# Electronic_Dice.net
KiCad netlist of a schematic drawn in Altium Designer
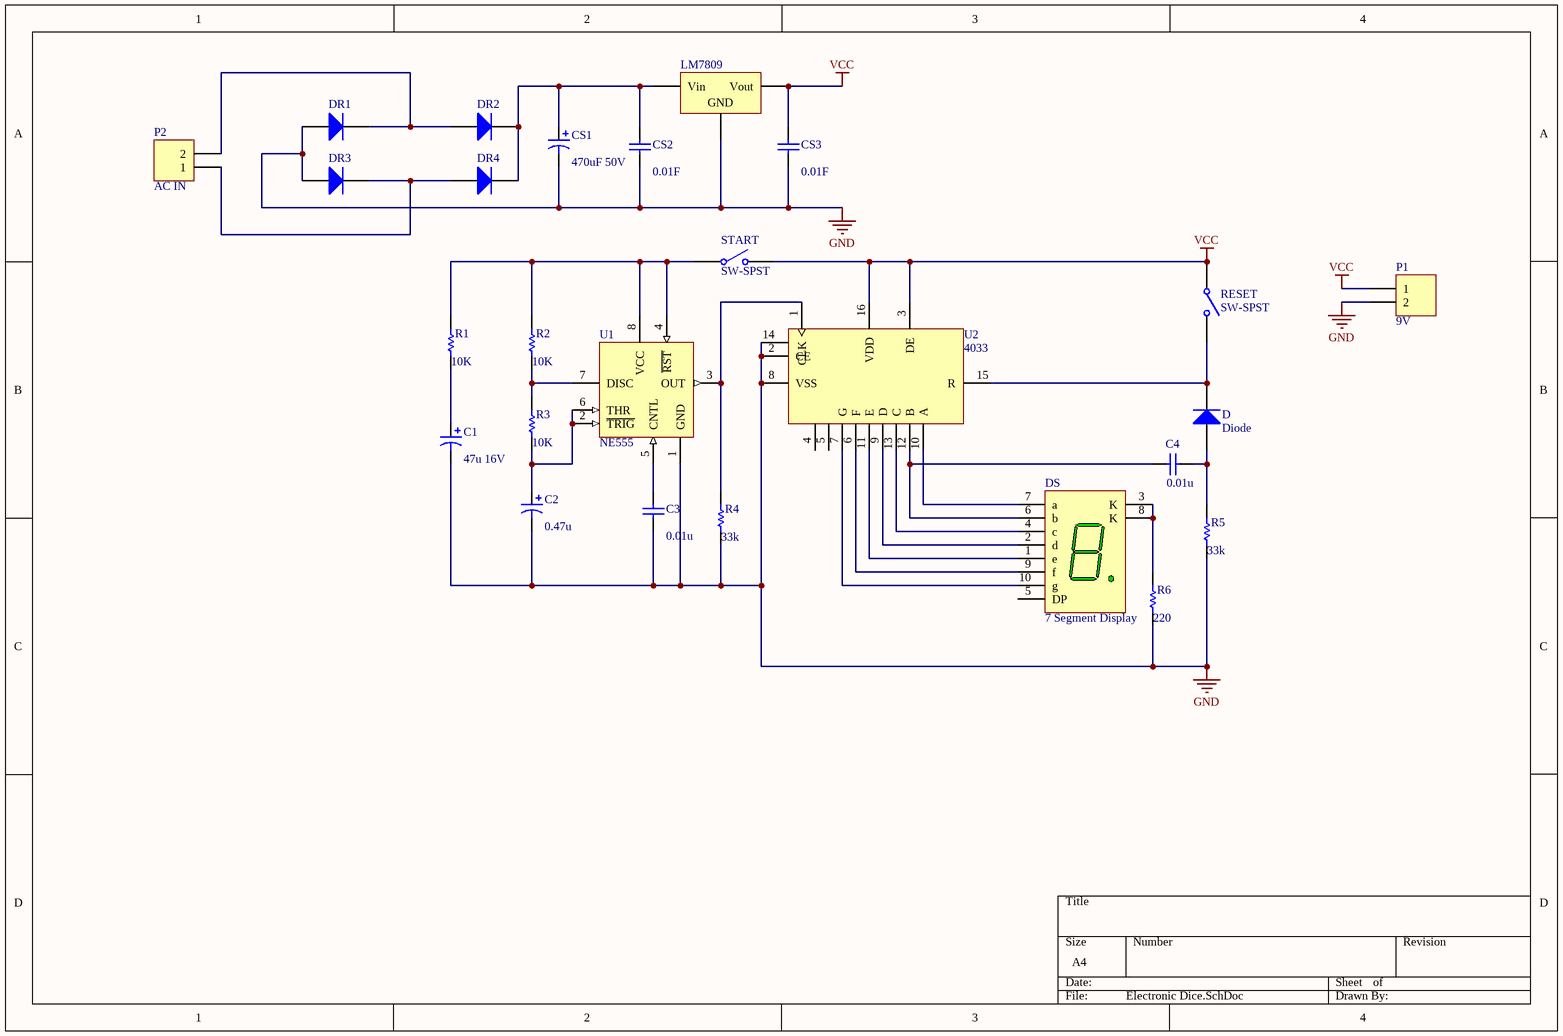
[diagram p0: Electronic Dice.SchDoc]

(export (version "E")
  (design (tool "Eeschema 10.0.6"))
  (components
    (comp (ref "C1")
      (value "47u 16V")
      (footprint "RAD-0.2")
      (description "Polarized Capacitor (Radial)")
      (fields (field (name "PUBLISHER") "Altium Limited"))
      (libsource (lib "Miscellaneous Devices") (part "Cap Pol1"))
    )
    (comp (ref "C2")
      (value "0.47u")
      (footprint "RAD-0.2")
      (description "Polarized Capacitor (Radial)")
      (fields (field (name "PUBLISHER") "Altium Limited"))
      (libsource (lib "Miscellaneous Devices") (part "Cap Pol1"))
    )
    (comp (ref "C3")
      (value "0.01u")
      (footprint "RAD-0.2")
      (description "Capacitor")
      (fields (field (name "PUBLISHER") "Altium Limited"))
      (libsource (lib "Miscellaneous Devices") (part "Cap"))
    )
    (comp (ref "C4")
      (value "0.01u")
      (footprint "RAD-0.2")
      (description "Capacitor")
      (fields (field (name "PUBLISHER") "Altium Limited"))
      (libsource (lib "Miscellaneous Devices") (part "Cap"))
    )
    (comp (ref "CS1")
      (value "470uF 50V")
      (footprint "RAD-0.3")
      (description "Polarized Capacitor (Radial)")
      (fields (field (name "PUBLISHER") "Altium Limited"))
      (libsource (lib "Miscellaneous Devices") (part "Cap Pol1"))
    )
    (comp (ref "CS2")
      (value "0.01F")
      (footprint "RAD-0.2")
      (description "Capacitor")
      (fields (field (name "PUBLISHER") "Altium Limited"))
      (libsource (lib "Miscellaneous Devices") (part "Cap"))
    )
    (comp (ref "CS3")
      (value "0.01F")
      (footprint "RAD-0.2")
      (description "Capacitor")
      (fields (field (name "PUBLISHER") "Altium Limited"))
      (libsource (lib "Miscellaneous Devices") (part "Cap"))
    )
    (comp (ref "D")
      (value "Diode")
      (footprint "DO-41")
      (description "Default Diode")
      (fields (field (name "PUBLISHER") "Altium Limited"))
      (libsource (lib "Miscellaneous Devices") (part "Diode"))
    )
    (comp (ref "DR1")
      (value "~")
      (footprint "DO-41")
      (description "1 Amp General Purpose Rectifier")
      (fields (field (name "PUBLISHER") "Altium Limited"))
      (libsource (lib "Miscellaneous Devices") (part "Diode 1N4007"))
    )
    (comp (ref "DR2")
      (value "~")
      (footprint "DO-41")
      (description "1 Amp General Purpose Rectifier")
      (fields (field (name "PUBLISHER") "Altium Limited"))
      (libsource (lib "Miscellaneous Devices") (part "Diode 1N4007"))
    )
    (comp (ref "DR3")
      (value "~")
      (footprint "DO-41")
      (description "1 Amp General Purpose Rectifier")
      (fields (field (name "PUBLISHER") "Altium Limited"))
      (libsource (lib "Miscellaneous Devices") (part "Diode 1N4007"))
    )
    (comp (ref "DR4")
      (value "~")
      (footprint "DO-41")
      (description "1 Amp General Purpose Rectifier")
      (fields (field (name "PUBLISHER") "Altium Limited"))
      (libsource (lib "Miscellaneous Devices") (part "Diode 1N4007"))
    )
    (comp (ref "DS")
      (value "7 Segment Display")
      (footprint "HDSP-51")
      (description "14.22 mm General Purpose Green 7-Segment Display: CC, RH DP")
      (fields (field (name "PUBLISHER") "Altium Limited"))
      (libsource (lib "Agilent LED Display 7-Segment, 1-Digit") (part "HDSP-513G"))
    )
    (comp (ref "LM7809")
      (value "~")
      (footprint "E3")
      (description "Voltage Regulator")
      (fields (field (name "PUBLISHER") "Altium Limited"))
      (libsource (lib "Miscellaneous Devices") (part "Volt Reg"))
    )
    (comp (ref "P1")
      (value "9V")
      (footprint "HDR1X2")
      (description "Header, 2-Pin")
      (fields (field (name "PUBLISHER") "Altium Limited"))
      (libsource (lib "") (part "Header 2_1"))
    )
    (comp (ref "P2")
      (value "AC IN")
      (footprint "HDR1X2")
      (description "Header, 2-Pin")
      (fields (field (name "PUBLISHER") "Altium Limited"))
      (libsource (lib "Miscellaneous Connectors") (part "Header 2"))
    )
    (comp (ref "R1")
      (value "10K")
      (footprint "R6.35x2.3")
      (description "Metal Oxide Film Resistor, 0.1 Ohm to 47k Ohm Range, 2% and 5% Tolerance, 0.5 W")
      (fields (field (name "PUBLISHER") "Altium Limited"))
      (libsource (lib "Panasonic Resistor") (part "ERG12"))
    )
    (comp (ref "R2")
      (value "10K")
      (footprint "R6.35x2.3")
      (description "Metal Oxide Film Resistor, 0.1 Ohm to 47k Ohm Range, 2% and 5% Tolerance, 0.5 W")
      (fields (field (name "PUBLISHER") "Altium Limited"))
      (libsource (lib "Panasonic Resistor") (part "ERG12"))
    )
    (comp (ref "R3")
      (value "10K")
      (footprint "R6.35x2.3")
      (description "Metal Oxide Film Resistor, 0.1 Ohm to 47k Ohm Range, 2% and 5% Tolerance, 0.5 W")
      (fields (field (name "PUBLISHER") "Altium Limited"))
      (libsource (lib "Panasonic Resistor") (part "ERG12"))
    )
    (comp (ref "R4")
      (value "33k")
      (footprint "R6.35x2.3")
      (description "Metal Oxide Film Resistor, 0.1 Ohm to 47k Ohm Range, 2% and 5% Tolerance, 0.5 W")
      (fields (field (name "PUBLISHER") "Altium Limited"))
      (libsource (lib "Panasonic Resistor") (part "ERG12"))
    )
    (comp (ref "R5")
      (value "33k")
      (footprint "R6.35x2.3")
      (description "Metal Oxide Film Resistor, 0.1 Ohm to 47k Ohm Range, 2% and 5% Tolerance, 0.5 W")
      (fields (field (name "PUBLISHER") "Altium Limited"))
      (libsource (lib "Panasonic Resistor") (part "ERG12"))
    )
    (comp (ref "R6")
      (value "220")
      (footprint "R6.35x2.3")
      (description "Metal Oxide Film Resistor, 0.1 Ohm to 47k Ohm Range, 2% and 5% Tolerance, 0.5 W")
      (fields (field (name "PUBLISHER") "Altium Limited"))
      (libsource (lib "Panasonic Resistor") (part "ERG12"))
    )
    (comp (ref "RESET")
      (value "SW-SPST")
      (footprint "SPST-2")
      (description "Single-Pole, Single-Throw Switch")
      (fields (field (name "PUBLISHER") "Altium Limited"))
      (libsource (lib "Miscellaneous Devices") (part "SW-SPST"))
    )
    (comp (ref "START")
      (value "SW-SPST")
      (footprint "SPST-2")
      (description "Single-Pole, Single-Throw Switch")
      (fields (field (name "PUBLISHER") "Altium Limited"))
      (libsource (lib "Miscellaneous Devices") (part "SW-SPST"))
    )
    (comp (ref "U1")
      (value "NE555")
      (footprint "626-05")
      (description "Timing Circuit")
      (fields (field (name "PUBLISHER") "Altium Limited"))
      (libsource (lib "ON Semi Logic Timer") (part "MC1455BP1"))
    )
    (comp (ref "U2")
      (value "4033")
      (footprint "J16A")
      (description "Synchronous Presettable Binary Counter")
      (fields (field (name "PUBLISHER") "Altium Limited"))
      (libsource (lib "FSC Logic Counter") (part "54F161ADM"))
    )
  )
  (nets
    (net (code "1") (name "GND") (class "Default")
      (node (ref "C1") (pin "2") (pinfunction "2_2") (pintype "passive"))
      (node (ref "C2") (pin "2") (pinfunction "2_2") (pintype "passive"))
      (node (ref "C3") (pin "1") (pinfunction "1_1") (pintype "passive"))
      (node (ref "CS1") (pin "2") (pinfunction "2_2") (pintype "passive"))
      (node (ref "CS2") (pin "1") (pinfunction "1_1") (pintype "passive"))
      (node (ref "CS3") (pin "1") (pinfunction "1_1") (pintype "passive"))
      (node (ref "DR1") (pin "1") (pinfunction "A_1") (pintype "passive"))
      (node (ref "DR3") (pin "1") (pinfunction "A_1") (pintype "passive"))
      (node (ref "LM7809") (pin "2") (pinfunction "GND_2") (pintype "passive"))
      (node (ref "P1") (pin "2") (pinfunction "2_2") (pintype "passive"))
      (node (ref "R4") (pin "1") (pinfunction "1_1") (pintype "passive"))
      (node (ref "R5") (pin "1") (pinfunction "1_1") (pintype "passive"))
      (node (ref "R6") (pin "1") (pinfunction "1_1") (pintype "passive"))
      (node (ref "U1") (pin "1") (pinfunction "GND_1") (pintype "power_in"))
      (node (ref "U2") (pin "14") (pintype "passive"))
      (node (ref "U2") (pin "2") (pinfunction "CE_2") (pintype "passive"))
      (node (ref "U2") (pin "8") (pinfunction "VSS_8") (pintype "power_in"))
    )
    (net (code "2") (name "Net-(C1-Pad1)") (class "Default")
      (node (ref "C1") (pin "1") (pinfunction "1_1") (pintype "passive"))
      (node (ref "R1") (pin "1") (pinfunction "1_1") (pintype "passive"))
    )
    (net (code "3") (name "Net-(D-A)") (class "Default")
      (node (ref "C4") (pin "1") (pinfunction "1_1") (pintype "passive"))
      (node (ref "D") (pin "1") (pinfunction "A_1") (pintype "passive"))
      (node (ref "R5") (pin "2") (pinfunction "2_2") (pintype "passive"))
    )
    (net (code "4") (name "Net-(D-K)") (class "Default")
      (node (ref "D") (pin "2") (pinfunction "K_2") (pintype "passive"))
      (node (ref "RESET") (pin "2") (pinfunction "NO_2") (pintype "passive"))
      (node (ref "U2") (pin "15") (pinfunction "R_15") (pintype "passive"))
    )
    (net (code "5") (name "Net-(DR1-K)") (class "Default")
      (node (ref "DR1") (pin "2") (pinfunction "K_2") (pintype "passive"))
      (node (ref "DR2") (pin "1") (pinfunction "A_1") (pintype "passive"))
      (node (ref "P2") (pin "2") (pinfunction "2_2") (pintype "passive"))
    )
    (net (code "6") (name "Net-(DR2-K)") (class "Default")
      (node (ref "CS1") (pin "1") (pinfunction "1_1") (pintype "passive"))
      (node (ref "CS2") (pin "2") (pinfunction "2_2") (pintype "passive"))
      (node (ref "DR2") (pin "2") (pinfunction "K_2") (pintype "passive"))
      (node (ref "DR4") (pin "2") (pinfunction "K_2") (pintype "passive"))
      (node (ref "LM7809") (pin "1") (pinfunction "Vin_1") (pintype "passive"))
    )
    (net (code "7") (name "Net-(DR3-K)") (class "Default")
      (node (ref "DR3") (pin "2") (pinfunction "K_2") (pintype "passive"))
      (node (ref "DR4") (pin "1") (pinfunction "A_1") (pintype "passive"))
      (node (ref "P2") (pin "1") (pinfunction "1_1") (pintype "passive"))
    )
    (net (code "8") (name "Net-(DS-K-Pad3)") (class "Default")
      (node (ref "DS") (pin "3") (pinfunction "K_3") (pintype "passive"))
      (node (ref "DS") (pin "8") (pinfunction "K_8") (pintype "passive"))
      (node (ref "R6") (pin "2") (pinfunction "2_2") (pintype "passive"))
    )
    (net (code "9") (name "Net-(DS-a)") (class "Default")
      (node (ref "DS") (pin "7") (pinfunction "a_7") (pintype "passive"))
      (node (ref "U2") (pin "10") (pinfunction "A_10") (pintype "passive"))
    )
    (net (code "10") (name "Net-(DS-b)") (class "Default")
      (node (ref "C4") (pin "2") (pinfunction "2_2") (pintype "passive"))
      (node (ref "DS") (pin "6") (pinfunction "b_6") (pintype "passive"))
      (node (ref "U2") (pin "12") (pinfunction "B_12") (pintype "passive"))
    )
    (net (code "11") (name "Net-(DS-c)") (class "Default")
      (node (ref "DS") (pin "4") (pinfunction "c_4") (pintype "passive"))
      (node (ref "U2") (pin "13") (pinfunction "C_13") (pintype "passive"))
    )
    (net (code "12") (name "Net-(DS-d)") (class "Default")
      (node (ref "DS") (pin "2") (pinfunction "d_2") (pintype "passive"))
      (node (ref "U2") (pin "9") (pinfunction "D_9") (pintype "passive"))
    )
    (net (code "13") (name "Net-(DS-e)") (class "Default")
      (node (ref "DS") (pin "1") (pinfunction "e_1") (pintype "passive"))
      (node (ref "U2") (pin "11") (pinfunction "E_11") (pintype "passive"))
    )
    (net (code "14") (name "Net-(DS-f)") (class "Default")
      (node (ref "DS") (pin "9") (pinfunction "f_9") (pintype "passive"))
      (node (ref "U2") (pin "6") (pinfunction "F_6") (pintype "passive"))
    )
    (net (code "15") (name "Net-(DS-g)") (class "Default")
      (node (ref "DS") (pin "10") (pinfunction "g_10") (pintype "passive"))
      (node (ref "U2") (pin "7") (pinfunction "G_7") (pintype "passive"))
    )
    (net (code "16") (name "Net-(START-COMMON)") (class "Default")
      (node (ref "R1") (pin "2") (pinfunction "2_2") (pintype "passive"))
      (node (ref "R2") (pin "2") (pinfunction "2_2") (pintype "passive"))
      (node (ref "START") (pin "1") (pinfunction "COMMON_1") (pintype "passive"))
      (node (ref "U1") (pin "4") (pinfunction "~{RST}_4") (pintype "input"))
      (node (ref "U1") (pin "8") (pinfunction "VCC_8") (pintype "power_in"))
    )
    (net (code "17") (name "Net-(U1-CNTL)") (class "Default")
      (node (ref "C3") (pin "2") (pinfunction "2_2") (pintype "passive"))
      (node (ref "U1") (pin "5") (pinfunction "CNTL_5") (pintype "input"))
    )
    (net (code "18") (name "Net-(U1-DISC)") (class "Default")
      (node (ref "R2") (pin "1") (pinfunction "1_1") (pintype "passive"))
      (node (ref "R3") (pin "2") (pinfunction "2_2") (pintype "passive"))
      (node (ref "U1") (pin "7") (pinfunction "DISC_7") (pintype "open_collector"))
    )
    (net (code "19") (name "Net-(U1-OUT)") (class "Default")
      (node (ref "R4") (pin "2") (pinfunction "2_2") (pintype "passive"))
      (node (ref "U1") (pin "3") (pinfunction "OUT_3") (pintype "output"))
      (node (ref "U2") (pin "1") (pinfunction "CLK_1") (pintype "passive"))
    )
    (net (code "20") (name "Net-(U1-THR)") (class "Default")
      (node (ref "C2") (pin "1") (pinfunction "1_1") (pintype "passive"))
      (node (ref "R3") (pin "1") (pinfunction "1_1") (pintype "passive"))
      (node (ref "U1") (pin "2") (pinfunction "~{TRIG}_2") (pintype "input"))
      (node (ref "U1") (pin "6") (pinfunction "THR_6") (pintype "input"))
    )
    (net (code "21") (name "VCC") (class "Default")
      (node (ref "CS3") (pin "2") (pinfunction "2_2") (pintype "passive"))
      (node (ref "LM7809") (pin "3") (pinfunction "Vout_3") (pintype "passive"))
      (node (ref "P1") (pin "1") (pinfunction "1_1") (pintype "passive"))
      (node (ref "RESET") (pin "1") (pinfunction "COMMON_1") (pintype "passive"))
      (node (ref "START") (pin "2") (pinfunction "NO_2") (pintype "passive"))
      (node (ref "U2") (pin "16") (pinfunction "VDD_16") (pintype "power_in"))
      (node (ref "U2") (pin "3") (pinfunction "DE_3") (pintype "passive"))
    )
    (net (code "22") (name "unconnected-(DS-DP-Pad5)") (class "Default")
      (node (ref "DS") (pin "5") (pinfunction "DP_5") (pintype "passive"))
    )
    (net (code "23") (name "unconnected-(U2-Pad4)") (class "Default")
      (node (ref "U2") (pin "4") (pintype "passive"))
    )
    (net (code "24") (name "unconnected-(U2-Pad5)") (class "Default")
      (node (ref "U2") (pin "5") (pintype "passive"))
    )
  )
)
